# sensor_sch.net
KiCad netlist of a schematic drawn in Altium Designer
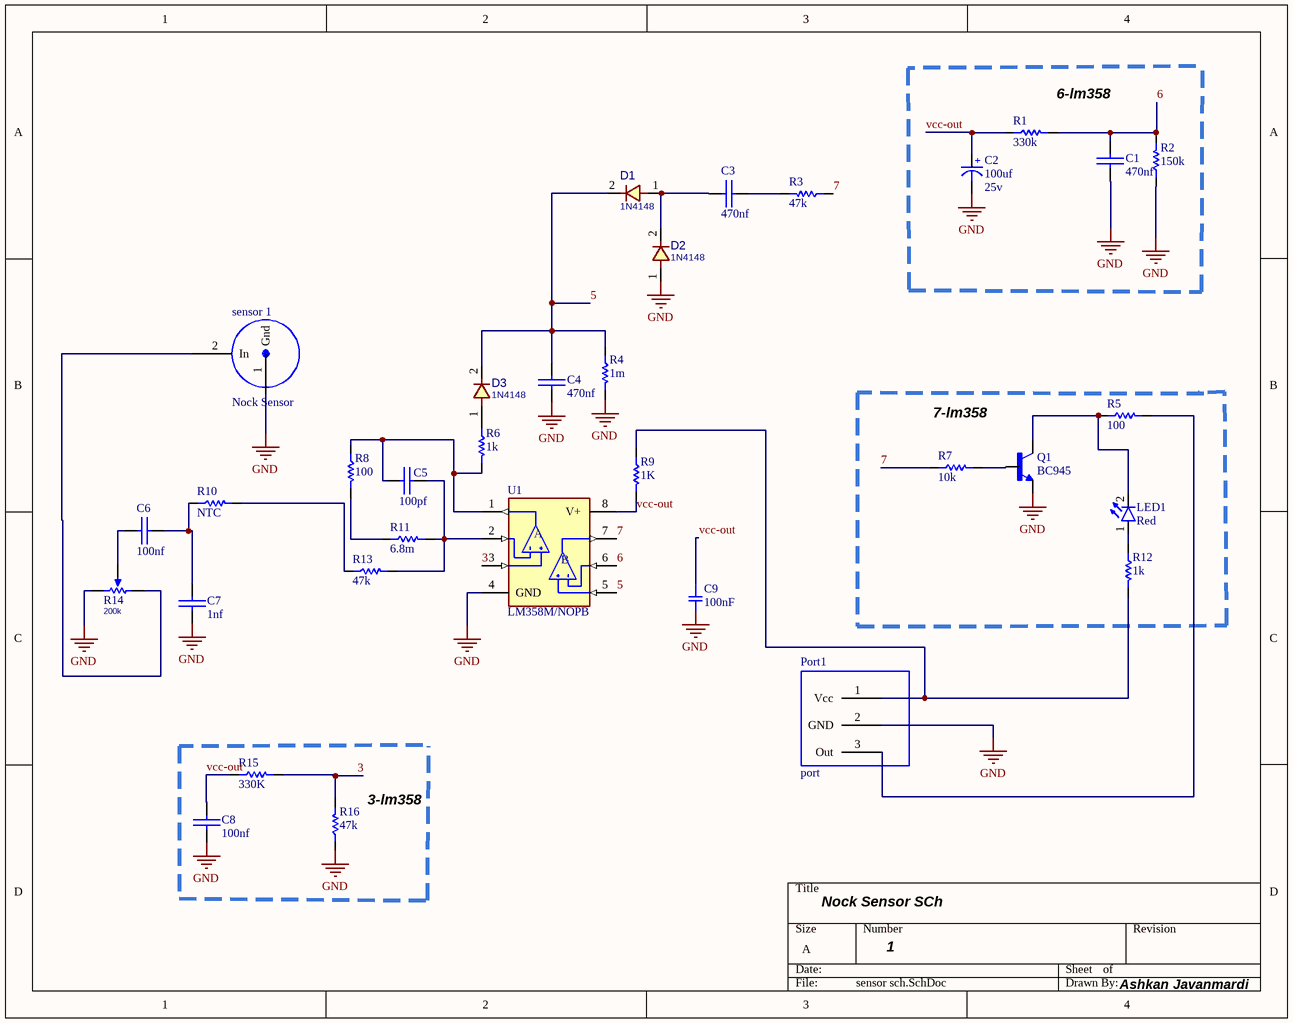
[diagram p0: sensor sch.SchDoc]

(export (version "E")
  (design (tool "Eeschema 10.0.6"))
  (components
    (comp (ref "C1")
      (value "470nf")
      (footprint "SMD_CAP_0805")
      (description "Bipolar Capacitor")
      (fields (field (name "VOLTAGE") "100V") (field (name "DESIGNER") "Saeid Jorablo"))
      (libsource (lib "My_Library") (part "Cap-Bipolar"))
    )
    (comp (ref "C2")
      (value "100uf")
      (footprint "cap 03")
      (description "Polar Capacitor")
      (fields (field (name "VOLTAGE") "25v") (field (name "DESIGNER") "Saeid Jorablo"))
      (libsource (lib "My_Library") (part "Cap-Polar"))
    )
    (comp (ref "C3")
      (value "470nf")
      (footprint "SMD_CAP_0805")
      (description "Bipolar Capacitor")
      (fields (field (name "VOLTAGE") "100V") (field (name "DESIGNER") "Saeid Jorablo"))
      (libsource (lib "My_Library") (part "Cap-Bipolar"))
    )
    (comp (ref "C4")
      (value "470nf")
      (footprint "SMD_CAP_0805")
      (description "Bipolar Capacitor")
      (fields (field (name "VOLTAGE") "100V") (field (name "DESIGNER") "Saeid Jorablo"))
      (libsource (lib "My_Library") (part "Cap-Bipolar"))
    )
    (comp (ref "C5")
      (value "100pf")
      (footprint "SMD_CAP_0805")
      (description "Bipolar Capacitor")
      (fields (field (name "VOLTAGE") "100V") (field (name "DESIGNER") "Saeid Jorablo"))
      (libsource (lib "My_Library") (part "Cap-Bipolar"))
    )
    (comp (ref "C6")
      (value "100nf")
      (footprint "SMD_CAP_0805")
      (description "Bipolar Capacitor")
      (fields (field (name "VOLTAGE") "100V") (field (name "DESIGNER") "Saeid Jorablo"))
      (libsource (lib "My_Library") (part "Cap-Bipolar"))
    )
    (comp (ref "C7")
      (value "1nf")
      (footprint "SMD_CAP_0805")
      (description "Bipolar Capacitor")
      (fields (field (name "VOLTAGE") "100V") (field (name "DESIGNER") "Saeid Jorablo"))
      (libsource (lib "My_Library") (part "Cap-Bipolar"))
    )
    (comp (ref "C8")
      (value "100nf")
      (footprint "SMD_CAP_0805")
      (description "Bipolar Capacitor")
      (fields (field (name "VOLTAGE") "100V") (field (name "DESIGNER") "Saeid Jorablo"))
      (libsource (lib "My_Library") (part "Cap-Bipolar"))
    )
    (comp (ref "C9")
      (value "100nF")
      (footprint "SMD-0805C")
      (description "CAP CER 0.015UF 250V X7T 0805")
      (fields
        (field (name "DIGI-KEY PART NUMBER") "490-13987-1-ND")
        (field (name "PART NUMBER") "GC321AD72E153KX01D")
      )
      (libsource (lib "capacitor_murata_0805") (part "GC321AD72E153KX01D"))
    )
    (comp (ref "D1")
      (value "1N4148")
      (footprint "D_SOD80")
      (description "DIODE, FAST SWTICHING, 0.3A, 0.5W")
      (fields (field (name "MANF") "MANF"))
      (libsource (lib "diode") (part "DIODE_SMD_1N4148"))
    )
    (comp (ref "D2")
      (value "1N4148")
      (footprint "D_SOD80")
      (description "DIODE, FAST SWTICHING, 0.3A, 0.5W")
      (fields (field (name "MANF") "MANF"))
      (libsource (lib "diode") (part "DIODE_SMD_1N4148"))
    )
    (comp (ref "D3")
      (value "1N4148")
      (footprint "D_SOD80")
      (description "DIODE, FAST SWTICHING, 0.3A, 0.5W")
      (fields (field (name "MANF") "MANF"))
      (libsource (lib "diode") (part "DIODE_SMD_1N4148"))
    )
    (comp (ref "LED1")
      (value "Red")
      (footprint "LED-3mm")
      (description "LED")
      (fields (field (name "COLOR") "Red") (field (name "DESIGNER") "Saeid Jorablo"))
      (libsource (lib "My_Library") (part "LED"))
    )
    (comp (ref "Port1") (value "port") (footprint "Port") (libsource (lib "Schlib1") (part "port")))
    (comp (ref "Q1")
      (value "BC945")
      (footprint "SOT23-BEC")
      (description "Bipolar _BJT_ Transistor NPN General Purpose Amplifier Surface Mount")
      (fields (field (name "MF") "ON Semiconductor") (field (name "MP") "BCW31"))
      (libsource (lib "BCW31_") (part "BCW31*"))
    )
    (comp (ref "R1")
      (value "330k")
      (footprint "RES 0805 (2012X06L)")
      (description "Resistor")
      (libsource (lib "My_Library") (part "Resistor"))
    )
    (comp (ref "R2")
      (value "150k")
      (footprint "RES 0805 (2012X06L)")
      (description "Resistor")
      (libsource (lib "My_Library") (part "Resistor"))
    )
    (comp (ref "R3")
      (value "47k")
      (footprint "RES 0805 (2012X06L)")
      (description "Resistor")
      (libsource (lib "My_Library") (part "Resistor"))
    )
    (comp (ref "R4")
      (value "1m")
      (footprint "RES 0805 (2012X06L)")
      (description "Resistor")
      (libsource (lib "My_Library") (part "Resistor"))
    )
    (comp (ref "R5")
      (value "100")
      (footprint "RES 0805 (2012X06L)")
      (description "Resistor")
      (libsource (lib "My_Library") (part "Resistor"))
    )
    (comp (ref "R6")
      (value "1k")
      (footprint "RES 0805 (2012X06L)")
      (description "Resistor")
      (libsource (lib "My_Library") (part "Resistor"))
    )
    (comp (ref "R7")
      (value "10k")
      (footprint "RES 0805 (2012X06L)")
      (description "Resistor")
      (libsource (lib "My_Library") (part "Resistor"))
    )
    (comp (ref "R8")
      (value "100")
      (footprint "RES 0805 (2012X06L)")
      (description "Resistor")
      (libsource (lib "My_Library") (part "Resistor"))
    )
    (comp (ref "R9")
      (value "1K")
      (footprint "RES 0805 (2012X06L)")
      (description "Resistor")
      (libsource (lib "My_Library") (part "Resistor"))
    )
    (comp (ref "R10")
      (value "NTC")
      (footprint "RES 0805 (2012X06L)")
      (description "Resistor")
      (libsource (lib "My_Library") (part "Resistor"))
    )
    (comp (ref "R11")
      (value "6.8m")
      (footprint "RES 0805 (2012X06L)")
      (description "Resistor")
      (libsource (lib "My_Library") (part "Resistor"))
    )
    (comp (ref "R12")
      (value "1k")
      (footprint "RES 0805 (2012X06L)")
      (description "Resistor")
      (libsource (lib "My_Library") (part "Resistor"))
    )
    (comp (ref "R13")
      (value "47k")
      (footprint "RES 0805 (2012X06L)")
      (description "Resistor")
      (libsource (lib "My_Library") (part "Resistor"))
    )
    (comp (ref "R14")
      (value "200k")
      (footprint "POT_7X5")
      (description "RESISTOR, THD, Potentiometer")
      (libsource (lib "resistor_pot_trimmer") (part "RES_THD_POT_7X5"))
    )
    (comp (ref "R15")
      (value "330K")
      (footprint "RES 0805 (2012X06L)")
      (description "Resistor")
      (libsource (lib "My_Library") (part "Resistor"))
    )
    (comp (ref "R16")
      (value "47k")
      (footprint "RES 0805 (2012X06L)")
      (description "Resistor")
      (libsource (lib "My_Library") (part "Resistor"))
    )
    (comp (ref "sensor 1")
      (value "Nock Sensor")
      (footprint "Sensor")
      (libsource (lib "Schlib1") (part "Nock Sensor"))
    )
    (comp (ref "U1")
      (value "LM358M/NOPB")
      (footprint "SOIC127P599X175-8N")
      (description "2-Channel, 1MHz, industry standard, 32V op amp 8-SOIC 0 to 70")
      (fields
        (field (name "DIGI-KEY_PART_NUMBER") "LM358MX/NOPBTR-ND")
        (field (name "MF") "Texas Instruments")
      )
      (libsource (lib "LM358M_NOPB") (part "LM358M/NOPB"))
    )
  )
  (nets
    (net (code "1") (name "/3") (class "Default")
      (node (ref "R15") (pin "2") (pinfunction "2_2") (pintype "passive"))
      (node (ref "R16") (pin "2") (pinfunction "2_2") (pintype "passive"))
      (node (ref "U1") (pin "3") (pinfunction "+INA_3") (pintype "input"))
    )
    (net (code "2") (name "/5") (class "Default")
      (node (ref "C4") (pin "1") (pinfunction "+_1") (pintype "passive"))
      (node (ref "D1") (pin "2") (pinfunction "2_2") (pintype "passive"))
      (node (ref "D3") (pin "2") (pinfunction "2_2") (pintype "passive"))
      (node (ref "R4") (pin "1") (pinfunction "1_1") (pintype "passive"))
      (node (ref "U1") (pin "5") (pinfunction "+INB_5") (pintype "input"))
    )
    (net (code "3") (name "/6") (class "Default")
      (node (ref "C1") (pin "2") (pinfunction "-_2") (pintype "passive"))
      (node (ref "R1") (pin "2") (pinfunction "2_2") (pintype "passive"))
      (node (ref "R2") (pin "2") (pinfunction "2_2") (pintype "passive"))
      (node (ref "U1") (pin "6") (pinfunction "-INB_6") (pintype "input"))
    )
    (net (code "4") (name "/7") (class "Default")
      (node (ref "R3") (pin "1") (pinfunction "1_1") (pintype "passive"))
      (node (ref "R7") (pin "1") (pinfunction "1_1") (pintype "passive"))
      (node (ref "U1") (pin "7") (pinfunction "OUTB_7") (pintype "output"))
    )
    (net (code "5") (name "/vcc-out") (class "Default")
      (node (ref "C2") (pin "1") (pinfunction "+_1") (pintype "passive"))
      (node (ref "C8") (pin "1") (pinfunction "+_1") (pintype "passive"))
      (node (ref "C9") (pin "1") (pinfunction "1_1") (pintype "passive"))
      (node (ref "R1") (pin "1") (pinfunction "1_1") (pintype "passive"))
      (node (ref "R15") (pin "1") (pinfunction "1_1") (pintype "passive"))
      (node (ref "R9") (pin "2") (pinfunction "2_2") (pintype "passive"))
      (node (ref "U1") (pin "8") (pinfunction "V+_8") (pintype "power_in"))
    )
    (net (code "6") (name "GND") (class "Default")
      (node (ref "C1") (pin "1") (pinfunction "+_1") (pintype "passive"))
      (node (ref "C2") (pin "2") (pinfunction "-_2") (pintype "passive"))
      (node (ref "C4") (pin "2") (pinfunction "-_2") (pintype "passive"))
      (node (ref "C7") (pin "2") (pinfunction "-_2") (pintype "passive"))
      (node (ref "C8") (pin "2") (pinfunction "-_2") (pintype "passive"))
      (node (ref "C9") (pin "2") (pinfunction "2_2") (pintype "passive"))
      (node (ref "D2") (pin "1") (pinfunction "1_1") (pintype "passive"))
      (node (ref "Port1") (pin "2") (pinfunction "GND_2") (pintype "passive"))
      (node (ref "Q1") (pin "E") (pinfunction "E_E") (pintype "passive"))
      (node (ref "R14") (pin "3") (pinfunction "BOT_3") (pintype "passive"))
      (node (ref "R16") (pin "1") (pinfunction "1_1") (pintype "passive"))
      (node (ref "R2") (pin "1") (pinfunction "1_1") (pintype "passive"))
      (node (ref "R4") (pin "2") (pinfunction "2_2") (pintype "passive"))
      (node (ref "U1") (pin "4") (pinfunction "GND_4") (pintype "power_in"))
      (node (ref "sensor 1") (pin "1") (pinfunction "Gnd_1") (pintype "passive"))
    )
    (net (code "7") (name "Net-(C3-+)") (class "Default")
      (node (ref "C3") (pin "1") (pinfunction "+_1") (pintype "passive"))
      (node (ref "R3") (pin "2") (pinfunction "2_2") (pintype "passive"))
    )
    (net (code "8") (name "Net-(C3--)") (class "Default")
      (node (ref "C3") (pin "2") (pinfunction "-_2") (pintype "passive"))
      (node (ref "D1") (pin "1") (pinfunction "1_1") (pintype "passive"))
      (node (ref "D2") (pin "2") (pinfunction "2_2") (pintype "passive"))
    )
    (net (code "9") (name "Net-(C5-+)") (class "Default")
      (node (ref "C5") (pin "1") (pinfunction "+_1") (pintype "passive"))
      (node (ref "R6") (pin "2") (pinfunction "2_2") (pintype "passive"))
      (node (ref "R8") (pin "1") (pinfunction "1_1") (pintype "passive"))
      (node (ref "U1") (pin "1") (pinfunction "OUTA_1") (pintype "output"))
    )
    (net (code "10") (name "Net-(C5--)") (class "Default")
      (node (ref "C5") (pin "2") (pinfunction "-_2") (pintype "passive"))
      (node (ref "R11") (pin "2") (pinfunction "2_2") (pintype "passive"))
      (node (ref "R13") (pin "2") (pinfunction "2_2") (pintype "passive"))
      (node (ref "U1") (pin "2") (pinfunction "-INA_2") (pintype "input"))
    )
    (net (code "11") (name "Net-(C6-+)") (class "Default")
      (node (ref "C6") (pin "1") (pinfunction "+_1") (pintype "passive"))
      (node (ref "C7") (pin "1") (pinfunction "+_1") (pintype "passive"))
      (node (ref "R10") (pin "1") (pinfunction "1_1") (pintype "passive"))
    )
    (net (code "12") (name "Net-(C6--)") (class "Default")
      (node (ref "C6") (pin "2") (pinfunction "-_2") (pintype "passive"))
      (node (ref "R14") (pin "2") (pinfunction "TAP_2") (pintype "passive"))
    )
    (net (code "13") (name "Net-(D3-Pad1)") (class "Default")
      (node (ref "D3") (pin "1") (pinfunction "1_1") (pintype "passive"))
      (node (ref "R6") (pin "1") (pinfunction "1_1") (pintype "passive"))
    )
    (net (code "14") (name "Net-(LED1-A)") (class "Default")
      (node (ref "LED1") (pin "1") (pinfunction "A_1") (pintype "passive"))
      (node (ref "R12") (pin "1") (pinfunction "1_1") (pintype "passive"))
    )
    (net (code "15") (name "Net-(LED1-K)") (class "Default")
      (node (ref "LED1") (pin "2") (pinfunction "K_2") (pintype "passive"))
      (node (ref "Q1") (pin "C") (pinfunction "C_C") (pintype "passive"))
      (node (ref "R5") (pin "1") (pinfunction "1_1") (pintype "passive"))
    )
    (net (code "16") (name "Net-(Port1-Out)") (class "Default")
      (node (ref "Port1") (pin "3") (pinfunction "Out_3") (pintype "passive"))
      (node (ref "R5") (pin "2") (pinfunction "2_2") (pintype "passive"))
    )
    (net (code "17") (name "Net-(Port1-Vcc)") (class "Default")
      (node (ref "Port1") (pin "1") (pinfunction "Vcc_1") (pintype "passive"))
      (node (ref "R9") (pin "1") (pinfunction "1_1") (pintype "passive"))
    )
    (net (code "18") (name "Net-(Q1-PadB)") (class "Default")
      (node (ref "Q1") (pin "B") (pinfunction "B_B") (pintype "passive"))
      (node (ref "R7") (pin "2") (pinfunction "2_2") (pintype "passive"))
    )
    (net (code "19") (name "Net-(R10-Pad2)") (class "Default")
      (node (ref "R10") (pin "2") (pinfunction "2_2") (pintype "passive"))
      (node (ref "R13") (pin "1") (pinfunction "1_1") (pintype "passive"))
    )
    (net (code "20") (name "Net-(R11-Pad1)") (class "Default")
      (node (ref "R11") (pin "1") (pinfunction "1_1") (pintype "passive"))
      (node (ref "R8") (pin "2") (pinfunction "2_2") (pintype "passive"))
    )
    (net (code "21") (name "Net-(R14-TOP)") (class "Default")
      (node (ref "R14") (pin "1") (pinfunction "TOP_1") (pintype "passive"))
      (node (ref "sensor 1") (pin "2") (pinfunction "In_2") (pintype "passive"))
    )
    (net (code "22") (name "unconnected-(R12-Pad2)") (class "Default")
      (node (ref "R12") (pin "2") (pinfunction "2_2") (pintype "passive"))
    )
  )
)
